# eagleExperiment1.net
KiCad netlist of a schematic drawn in EAGLE
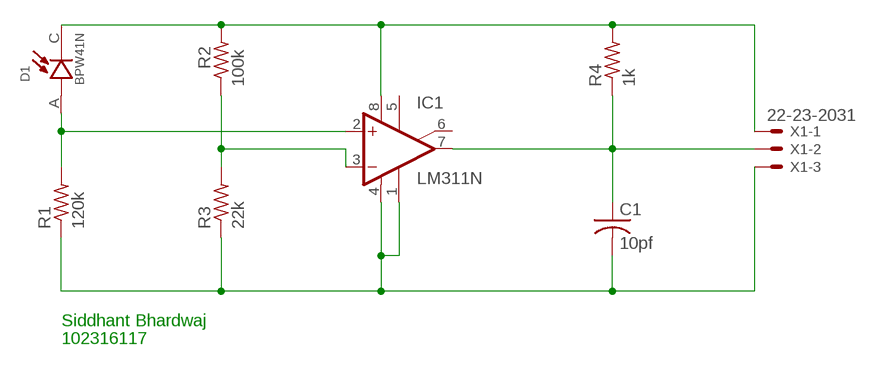
[diagram p0: schematic, sheet 1]

(export (version "E")
  (design (tool "Eeschema 10.0.6"))
  (components
    (comp (ref "C1")
      (value "10pf")
      (footprint "eagle-import:C025-025X050")
      (libsource (lib "eagle-import") (part "C-US025-025X050"))
    )
    (comp (ref "D1")
      (value "BPW41N")
      (footprint "eagle-import:DIO_BPW41N")
      (fields (field (name "MF") "Vishay Semiconductor Opto Division"))
      (libsource (lib "eagle-import") (part "BPW41N"))
    )
    (comp (ref "IC1")
      (value "LM311N")
      (footprint "eagle-import:DIL08")
      (libsource (lib "eagle-import") (part "LM311N"))
    )
    (comp (ref "R1")
      (value "120k")
      (footprint "eagle-import:0204_5")
      (libsource (lib "eagle-import") (part "R-US_0204/5"))
    )
    (comp (ref "R2")
      (value "100k")
      (footprint "eagle-import:0204_5")
      (libsource (lib "eagle-import") (part "R-US_0204/5"))
    )
    (comp (ref "R3")
      (value "22k")
      (footprint "eagle-import:0204_5")
      (libsource (lib "eagle-import") (part "R-US_0204/5"))
    )
    (comp (ref "R4")
      (value "1k")
      (footprint "eagle-import:0204_5")
      (libsource (lib "eagle-import") (part "R-US_0204/5"))
    )
    (comp (ref "X1")
      (value "22-23-2031")
      (footprint "eagle-import:22-23-2031")
      (fields (field (name "MF") "MOLEX"))
      (libsource (lib "eagle-import") (part "22-23-2031"))
    )
  )
  (nets
    (net (code "1") (name "Net-(IC1-+IN)") (class "Default")
      (node (ref "D1") (pin "A") (pinfunction "A_A") (pintype "passive"))
      (node (ref "IC1") (pin "2") (pinfunction "+IN_2") (pintype "input"))
      (node (ref "R1") (pin "2") (pinfunction "2_2") (pintype "passive"))
    )
    (net (code "2") (name "Net-(IC1--IN)") (class "Default")
      (node (ref "IC1") (pin "3") (pinfunction "-IN_3") (pintype "input"))
      (node (ref "R2") (pin "1") (pinfunction "1_1") (pintype "passive"))
      (node (ref "R3") (pin "2") (pinfunction "2_2") (pintype "passive"))
    )
    (net (code "3") (name "Net-(IC1-GND)") (class "Default")
      (node (ref "C1") (pin "2") (pinfunction "2_2") (pintype "passive"))
      (node (ref "IC1") (pin "1") (pinfunction "GND_1") (pintype "passive"))
      (node (ref "IC1") (pin "4") (pinfunction "V-_4") (pintype "power_in"))
      (node (ref "R1") (pin "1") (pinfunction "1_1") (pintype "passive"))
      (node (ref "R3") (pin "1") (pinfunction "1_1") (pintype "passive"))
      (node (ref "X1") (pin "3") (pinfunction "S_3") (pintype "passive"))
    )
    (net (code "4") (name "Net-(IC1-OUT)") (class "Default")
      (node (ref "C1") (pin "1") (pinfunction "1_1") (pintype "passive"))
      (node (ref "IC1") (pin "7") (pinfunction "OUT_7") (pintype "output"))
      (node (ref "R4") (pin "1") (pinfunction "1_1") (pintype "passive"))
      (node (ref "X1") (pin "2") (pinfunction "S_2") (pintype "passive"))
    )
    (net (code "5") (name "Net-(IC1-V+)") (class "Default")
      (node (ref "D1") (pin "C") (pinfunction "C_C") (pintype "passive"))
      (node (ref "IC1") (pin "8") (pinfunction "V+_8") (pintype "power_in"))
      (node (ref "R2") (pin "2") (pinfunction "2_2") (pintype "passive"))
      (node (ref "R4") (pin "2") (pinfunction "2_2") (pintype "passive"))
      (node (ref "X1") (pin "1") (pinfunction "S_1") (pintype "passive"))
    )
    (net (code "6") (name "unconnected-(IC1-ON-Pad5)") (class "Default")
      (node (ref "IC1") (pin "5") (pinfunction "ON_5") (pintype "passive"))
    )
    (net (code "7") (name "unconnected-(IC1-ON{slash}STR-Pad6)") (class "Default")
      (node (ref "IC1") (pin "6") (pinfunction "ON/STR_6") (pintype "passive"))
    )
  )
)
